# ProDocument_LTC2220_ADA_V1_2025-01-04.net
KiCad netlist of a schematic drawn in EasyEDA Pro
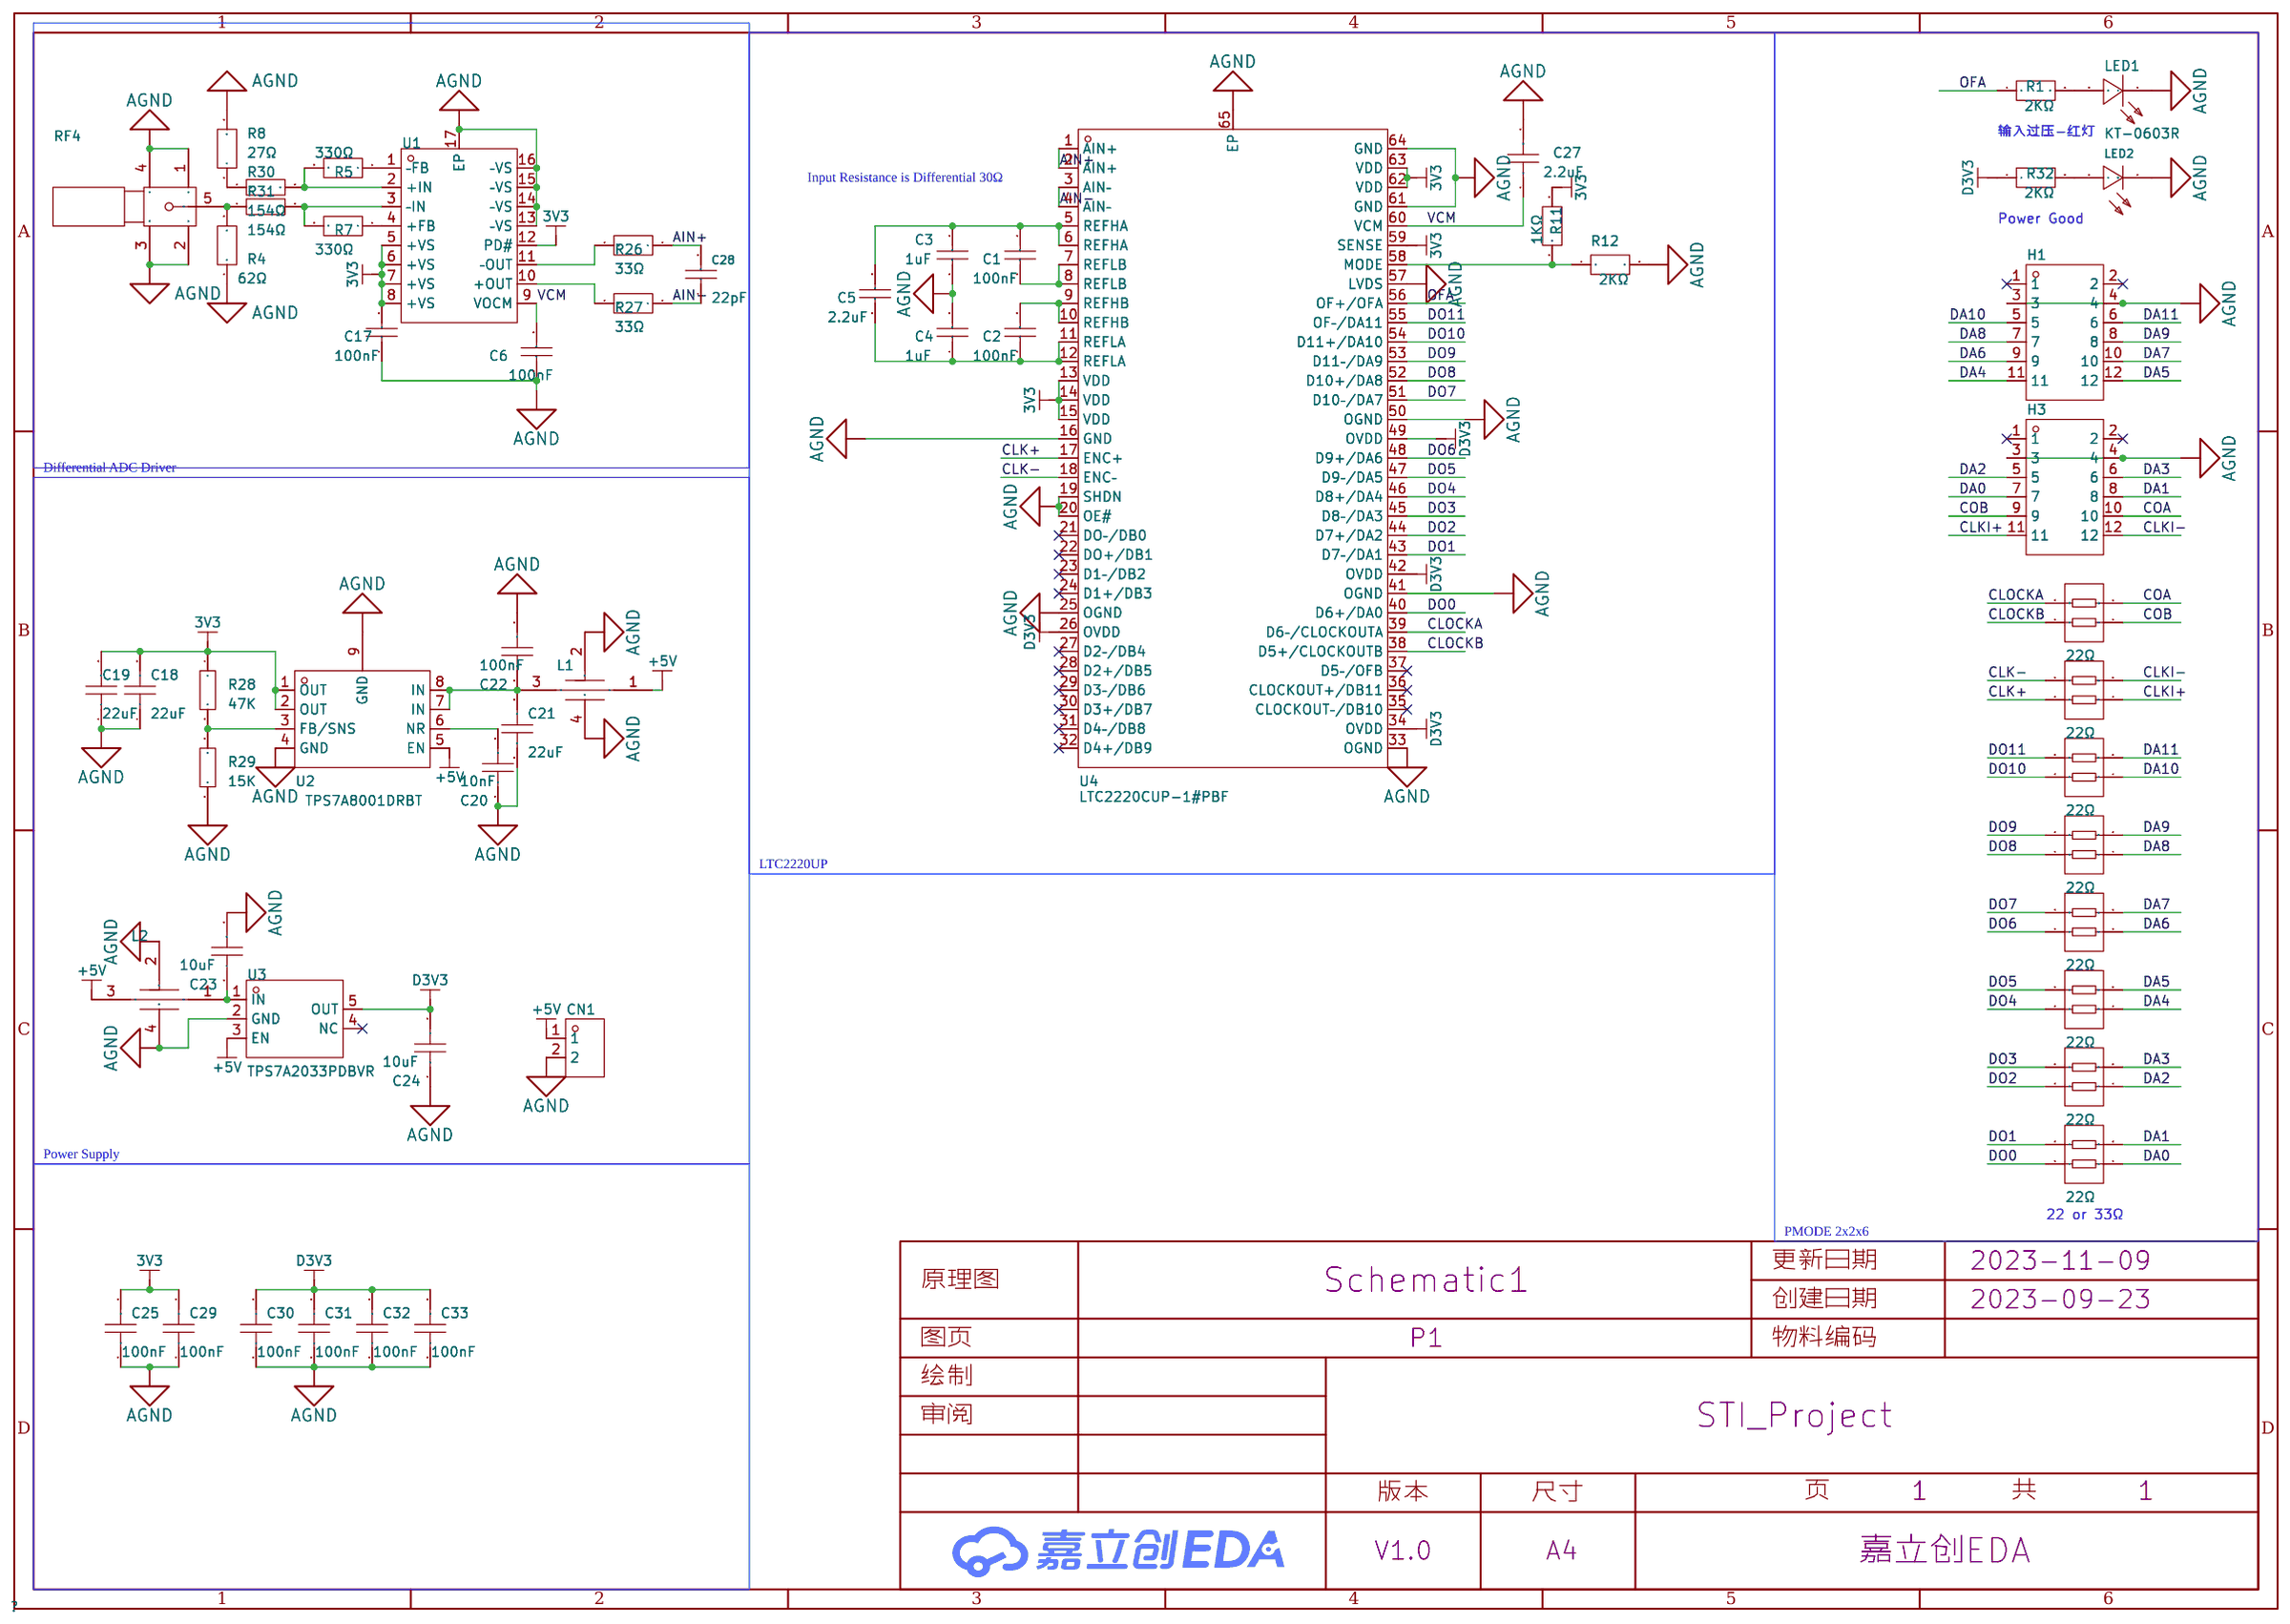
[diagram p0: schematic sheet]

(export (version "E")
  (design (tool "Eeschema 10.0.6"))
  (components
    (comp (ref "C1")
      (value "100nF")
      (footprint "easyedapro:C0402")
      (description "容值:100nF;精度:±10%;额定电压:16V;材质(温度系数):X7R;")
      (fields
        (field (name "Manufacturer Part") "GCM155R71C104KA40D")
        (field (name "Manufacturer") "muRata(村田)")
      )
      (libsource (lib "easyedapro") (part "GCM155R71C104KA40D"))
    )
    (comp (ref "C2")
      (value "100nF")
      (footprint "easyedapro:C0402")
      (description "容值:100nF;精度:±10%;额定电压:16V;材质(温度系数):X7R;")
      (fields
        (field (name "Manufacturer Part") "GCM155R71C104KA40D")
        (field (name "Manufacturer") "muRata(村田)")
      )
      (libsource (lib "easyedapro") (part "GCM155R71C104KA40D"))
    )
    (comp (ref "C3")
      (value "1uF")
      (footprint "easyedapro:C0402")
      (description "容值:100nF;精度:±10%;额定电压:16V;材质(温度系数):X7R;")
      (fields
        (field (name "Manufacturer Part") "GCM155R71C104KA40D")
        (field (name "Manufacturer") "muRata(村田)")
      )
      (libsource (lib "easyedapro") (part "GCM155R71C104KA40D"))
    )
    (comp (ref "C4")
      (value "1uF")
      (footprint "easyedapro:C0402")
      (description "容值:100nF;精度:±10%;额定电压:16V;材质(温度系数):X7R;")
      (fields
        (field (name "Manufacturer Part") "GCM155R71C104KA40D")
        (field (name "Manufacturer") "muRata(村田)")
      )
      (libsource (lib "easyedapro") (part "GCM155R71C104KA40D"))
    )
    (comp (ref "C5")
      (value "2.2uF")
      (footprint "easyedapro:C0402")
      (description "容值:100nF;精度:±10%;额定电压:16V;材质(温度系数):X7R;")
      (fields
        (field (name "Manufacturer Part") "GCM155R71C104KA40D")
        (field (name "Manufacturer") "muRata(村田)")
      )
      (libsource (lib "easyedapro") (part "GCM155R71C104KA40D"))
    )
    (comp (ref "C6")
      (value "100nF")
      (footprint "easyedapro:C0402")
      (description "容值:100nF;精度:±10%;额定电压:16V;材质(温度系数):X7R;")
      (fields
        (field (name "Manufacturer Part") "GCM155R71C104KA40D")
        (field (name "Manufacturer") "muRata(村田)")
      )
      (libsource (lib "easyedapro") (part "GCM155R71C104KA40D"))
    )
    (comp (ref "C17")
      (value "100nF")
      (footprint "easyedapro:C0402")
      (description "容值:100nF;精度:±10%;额定电压:16V;材质(温度系数):X7R;")
      (fields
        (field (name "Manufacturer Part") "GCM155R71C104KA40D")
        (field (name "Manufacturer") "muRata(村田)")
      )
      (libsource (lib "easyedapro") (part "GCM155R71C104KA40D"))
    )
    (comp (ref "C18")
      (value "22uF")
      (footprint "easyedapro:C0805")
      (description "容值:22uF;精度:±20%;额定电压:25V;材质(温度系数):X5R;")
      (fields
        (field (name "Manufacturer Part") "CL21A226MAQNNNE")
        (field (name "Manufacturer") "SAMSUNG(三星)")
      )
      (libsource (lib "easyedapro") (part "CL21A226MAQNNNE"))
    )
    (comp (ref "C19")
      (value "22uF")
      (footprint "easyedapro:C0805")
      (description "容值:22uF;精度:±20%;额定电压:25V;材质(温度系数):X5R;")
      (fields
        (field (name "Manufacturer Part") "CL21A226MAQNNNE")
        (field (name "Manufacturer") "SAMSUNG(三星)")
      )
      (libsource (lib "easyedapro") (part "CL21A226MAQNNNE"))
    )
    (comp (ref "C20")
      (value "10nF")
      (footprint "easyedapro:C0402")
      (libsource (lib "easyedapro") (part "CapAcitance"))
    )
    (comp (ref "C21")
      (value "22uF")
      (footprint "easyedapro:C0805")
      (description "容值:22uF;精度:±20%;额定电压:25V;材质(温度系数):X5R;")
      (fields
        (field (name "Manufacturer Part") "CL21A226MAQNNNE")
        (field (name "Manufacturer") "SAMSUNG(三星)")
      )
      (libsource (lib "easyedapro") (part "CL21A226MAQNNNE"))
    )
    (comp (ref "C22")
      (value "100nF")
      (footprint "easyedapro:C0402")
      (libsource (lib "easyedapro") (part "CapAcitance"))
    )
    (comp (ref "C23")
      (value "10uF")
      (footprint "easyedapro:C0402")
      (libsource (lib "easyedapro") (part "CapAcitance"))
    )
    (comp (ref "C24")
      (value "10uF")
      (footprint "easyedapro:C0402")
      (libsource (lib "easyedapro") (part "CapAcitance"))
    )
    (comp (ref "C25")
      (value "100nF")
      (footprint "easyedapro:C0402")
      (libsource (lib "easyedapro") (part "CapAcitance"))
    )
    (comp (ref "C27")
      (value "2.2uF")
      (footprint "easyedapro:C0402")
      (libsource (lib "easyedapro") (part "CapAcitance"))
    )
    (comp (ref "C28")
      (value "22pF")
      (footprint "easyedapro:C0402")
      (description "容值:22pF;精度:±5%;额定电压:50V;材质(温度系数):C0G;")
      (fields (field (name "Manufacturer Part") "0402CG220J500NT") (field (name "Manufacturer") "FH(风华)"))
      (libsource (lib "easyedapro") (part "0402CG220J500NT"))
    )
    (comp (ref "C29")
      (value "100nF")
      (footprint "easyedapro:C0402")
      (libsource (lib "easyedapro") (part "CapAcitance"))
    )
    (comp (ref "C30")
      (value "100nF")
      (footprint "easyedapro:C0402")
      (libsource (lib "easyedapro") (part "CapAcitance"))
    )
    (comp (ref "C31")
      (value "100nF")
      (footprint "easyedapro:C0402")
      (libsource (lib "easyedapro") (part "CapAcitance"))
    )
    (comp (ref "C32")
      (value "100nF")
      (footprint "easyedapro:C0402")
      (libsource (lib "easyedapro") (part "CapAcitance"))
    )
    (comp (ref "C33")
      (value "100nF")
      (footprint "easyedapro:C0402")
      (libsource (lib "easyedapro") (part "CapAcitance"))
    )
    (comp (ref "CN1")
      (value "M2510V-02P")
      (footprint "easyedapro:CONN-TH_M2510V-02P")
      (description "参考系列:-;间距:2.54mm;插针结构:1x2P;排数:1;每排PIN数:2;行距:-;公母:公型插针;安装方式:直插;额定电流:3A;工作温度范围:-25~+85;")
      (fields (field (name "Manufacturer") "XFCN(台湾兴飞)"))
      (libsource (lib "easyedapro") (part "M2510V-02P"))
    )
    (comp (ref "H1")
      (value "DZ254W-22-12-69")
      (footprint "easyedapro:HDR-TH_12P-P2.54-H-M-R2-C6-S2.54-W12.5")
      (fields (field (name "Manufacturer") "DEALON(德艺隆)"))
      (libsource (lib "easyedapro") (part "DZ254W-22-12-69"))
    )
    (comp (ref "H3")
      (value "DZ254W-22-12-69")
      (footprint "easyedapro:HDR-TH_12P-P2.54-H-M-R2-C6-S2.54-W12.5")
      (fields (field (name "Manufacturer") "DEALON(德艺隆)"))
      (libsource (lib "easyedapro") (part "DZ254W-22-12-69"))
    )
    (comp (ref "L1")
      (value "NFM21PC104R1E3D")
      (footprint "easyedapro:CAP-SMD_4P-L2.0-W1.25")
      (description "电容量:100nF;精度:±20%;直流电阻:30mΩ;")
      (fields (field (name "Manufacturer") "muRata(村田)"))
      (libsource (lib "easyedapro") (part "NFM21PC104R1E3D"))
    )
    (comp (ref "L2")
      (value "NFM21PC104R1E3D")
      (footprint "easyedapro:CAP-SMD_4P-L2.0-W1.25")
      (description "电容量:100nF;精度:±20%;直流电阻:30mΩ;")
      (fields (field (name "Manufacturer") "muRata(村田)"))
      (libsource (lib "easyedapro") (part "NFM21PC104R1E3D"))
    )
    (comp (ref "LED1")
      (value "KT-0603R")
      (footprint "easyedapro:LED0603-RD")
      (description "发光颜色:红灯;二极管配置:-;透镜颜色:-;主波长:-;色温:-;功率:-;发光角度:-;安装方式:-;工作温度:-40°C~+85°C;")
      (fields (field (name "Manufacturer") "KENTO"))
      (libsource (lib "easyedapro") (part "KT-0603R"))
    )
    (comp (ref "LED2")
      (value "19-217/GHC-YR1S2/3T")
      (footprint "easyedapro:LED0603-RD")
      (description "发光颜色:翠绿;二极管配置:-;主波长:520nm~535nm;色温:-;功率:110mW;安装方式:-;")
      (fields (field (name "Manufacturer") "EVERLIGHT(亿光)"))
      (libsource (lib "easyedapro") (part "19-217/GHC-YR1S2/3T"))
    )
    (comp (ref "R1")
      (value "2KΩ")
      (footprint "easyedapro:R0402")
      (description "阻值:1kΩ;精度:±0.1%;温度系数:±25ppm/;")
      (fields (field (name "Manufacturer Part") "ARG02BTC1001") (field (name "Manufacturer") "Viking(光颉)"))
      (libsource (lib "easyedapro") (part "ARG02BTC1001"))
    )
    (comp (ref "R4")
      (value "62Ω")
      (footprint "easyedapro:R0402")
      (description "阻值:1kΩ;精度:±0.1%;温度系数:±25ppm/;")
      (fields (field (name "Manufacturer Part") "ARG02BTC1001") (field (name "Manufacturer") "Viking(光颉)"))
      (libsource (lib "easyedapro") (part "ARG02BTC1001"))
    )
    (comp (ref "R5")
      (value "330Ω")
      (footprint "easyedapro:R0402")
      (description "阻值:1kΩ;精度:±0.1%;温度系数:±25ppm/;")
      (fields (field (name "Manufacturer Part") "ARG02BTC1001") (field (name "Manufacturer") "Viking(光颉)"))
      (libsource (lib "easyedapro") (part "ARG02BTC1001"))
    )
    (comp (ref "R7")
      (value "330Ω")
      (footprint "easyedapro:R0402")
      (description "阻值:1kΩ;精度:±0.1%;温度系数:±25ppm/;")
      (fields (field (name "Manufacturer Part") "ARG02BTC1001") (field (name "Manufacturer") "Viking(光颉)"))
      (libsource (lib "easyedapro") (part "ARG02BTC1001"))
    )
    (comp (ref "R8")
      (value "27Ω")
      (footprint "easyedapro:R0402")
      (description "阻值:1kΩ;精度:±0.1%;温度系数:±25ppm/;")
      (fields (field (name "Manufacturer Part") "ARG02BTC1001") (field (name "Manufacturer") "Viking(光颉)"))
      (libsource (lib "easyedapro") (part "ARG02BTC1001"))
    )
    (comp (ref "R11")
      (value "1KΩ")
      (footprint "easyedapro:R0402")
      (description "阻值:1kΩ;精度:±0.1%;温度系数:±25ppm/;")
      (fields (field (name "Manufacturer Part") "ARG02BTC1001") (field (name "Manufacturer") "Viking(光颉)"))
      (libsource (lib "easyedapro") (part "ARG02BTC1001"))
    )
    (comp (ref "R12")
      (value "2KΩ")
      (footprint "easyedapro:R0402")
      (description "阻值:1kΩ;精度:±0.1%;温度系数:±25ppm/;")
      (fields (field (name "Manufacturer Part") "ARG02BTC1001") (field (name "Manufacturer") "Viking(光颉)"))
      (libsource (lib "easyedapro") (part "ARG02BTC1001"))
    )
    (comp (ref "R26")
      (value "33Ω")
      (footprint "easyedapro:R0402")
      (description "阻值:1kΩ;精度:±0.1%;温度系数:±25ppm/;")
      (fields (field (name "Manufacturer Part") "ARG02BTC1001") (field (name "Manufacturer") "Viking(光颉)"))
      (libsource (lib "easyedapro") (part "ARG02BTC1001"))
    )
    (comp (ref "R27")
      (value "33Ω")
      (footprint "easyedapro:R0402")
      (description "阻值:1kΩ;精度:±0.1%;温度系数:±25ppm/;")
      (fields (field (name "Manufacturer Part") "ARG02BTC1001") (field (name "Manufacturer") "Viking(光颉)"))
      (libsource (lib "easyedapro") (part "ARG02BTC1001"))
    )
    (comp (ref "R28") (value "47K") (footprint "easyedapro:R0402") (libsource (lib "easyedapro") (part "电阻")))
    (comp (ref "R29") (value "15K") (footprint "easyedapro:R0402") (libsource (lib "easyedapro") (part "电阻")))
    (comp (ref "R30")
      (value "154Ω")
      (footprint "easyedapro:R0402")
      (description "电阻类型:厚膜电阻;阻值:154Ω;精度:±1%;功率:62.5mW;")
      (fields (field (name "Manufacturer Part") "AC0402FR-07154RL") (field (name "Manufacturer") "YAGEO(国巨)"))
      (libsource (lib "easyedapro") (part "AC0402FR-07154RL"))
    )
    (comp (ref "R31")
      (value "154Ω")
      (footprint "easyedapro:R0402")
      (description "电阻类型:厚膜电阻;阻值:154Ω;精度:±1%;功率:62.5mW;")
      (fields (field (name "Manufacturer Part") "AC0402FR-07154RL") (field (name "Manufacturer") "YAGEO(国巨)"))
      (libsource (lib "easyedapro") (part "AC0402FR-07154RL"))
    )
    (comp (ref "R32")
      (value "2KΩ")
      (footprint "easyedapro:R0402")
      (description "阻值:1kΩ;精度:±0.1%;温度系数:±25ppm/;")
      (fields (field (name "Manufacturer Part") "ARG02BTC1001") (field (name "Manufacturer") "Viking(光颉)"))
      (libsource (lib "easyedapro") (part "ARG02BTC1001"))
    )
    (comp (ref "RF4")
      (value "KH-SMA-KE5.4")
      (footprint "easyedapro:SMA-TH_KH-SMA-KE-Z")
      (description "SMA板端 SMA板端 镀金半牙正脚直插SMA母针板端L=16.8MM 牙长5.4MM")
      (fields (field (name "Manufacturer") "kinghelm(金航标)"))
      (libsource (lib "easyedapro") (part "KH-SMA-KE5.4"))
    )
    (comp (ref "RN1")
      (value "22Ω")
      (footprint "easyedapro:RES-ARRAY-SMD_0402-4P-L1.0-W1.0-BL")
      (description "阻值:22Ω;精度:±1%;单个元件功率:62.5mW;电阻器数:2;")
      (fields
        (field (name "Manufacturer Part") "2D02WGF220JTCE")
        (field (name "Manufacturer") "UNI-ROYAL(厚声)")
      )
      (libsource (lib "easyedapro") (part "2D02WGF220JTCE"))
    )
    (comp (ref "RN2")
      (value "22Ω")
      (footprint "easyedapro:RES-ARRAY-SMD_0402-4P-L1.0-W1.0-BL")
      (description "阻值:22Ω;精度:±1%;单个元件功率:62.5mW;电阻器数:2;")
      (fields
        (field (name "Manufacturer Part") "2D02WGF220JTCE")
        (field (name "Manufacturer") "UNI-ROYAL(厚声)")
      )
      (libsource (lib "easyedapro") (part "2D02WGF220JTCE"))
    )
    (comp (ref "RN3")
      (value "22Ω")
      (footprint "easyedapro:RES-ARRAY-SMD_0402-4P-L1.0-W1.0-BL")
      (description "阻值:22Ω;精度:±1%;单个元件功率:62.5mW;电阻器数:2;")
      (fields
        (field (name "Manufacturer Part") "2D02WGF220JTCE")
        (field (name "Manufacturer") "UNI-ROYAL(厚声)")
      )
      (libsource (lib "easyedapro") (part "2D02WGF220JTCE"))
    )
    (comp (ref "RN4")
      (value "22Ω")
      (footprint "easyedapro:RES-ARRAY-SMD_0402-4P-L1.0-W1.0-BL")
      (description "阻值:22Ω;精度:±1%;单个元件功率:62.5mW;电阻器数:2;")
      (fields
        (field (name "Manufacturer Part") "2D02WGF220JTCE")
        (field (name "Manufacturer") "UNI-ROYAL(厚声)")
      )
      (libsource (lib "easyedapro") (part "2D02WGF220JTCE"))
    )
    (comp (ref "RN5")
      (value "22Ω")
      (footprint "easyedapro:RES-ARRAY-SMD_0402-4P-L1.0-W1.0-BL")
      (description "阻值:22Ω;精度:±1%;单个元件功率:62.5mW;电阻器数:2;")
      (fields
        (field (name "Manufacturer Part") "2D02WGF220JTCE")
        (field (name "Manufacturer") "UNI-ROYAL(厚声)")
      )
      (libsource (lib "easyedapro") (part "2D02WGF220JTCE"))
    )
    (comp (ref "RN6")
      (value "22Ω")
      (footprint "easyedapro:RES-ARRAY-SMD_0402-4P-L1.0-W1.0-BL")
      (description "阻值:22Ω;精度:±1%;单个元件功率:62.5mW;电阻器数:2;")
      (fields
        (field (name "Manufacturer Part") "2D02WGF220JTCE")
        (field (name "Manufacturer") "UNI-ROYAL(厚声)")
      )
      (libsource (lib "easyedapro") (part "2D02WGF220JTCE"))
    )
    (comp (ref "RN7")
      (value "22Ω")
      (footprint "easyedapro:RES-ARRAY-SMD_0402-4P-L1.0-W1.0-BL")
      (description "阻值:22Ω;精度:±1%;单个元件功率:62.5mW;电阻器数:2;")
      (fields
        (field (name "Manufacturer Part") "2D02WGF220JTCE")
        (field (name "Manufacturer") "UNI-ROYAL(厚声)")
      )
      (libsource (lib "easyedapro") (part "2D02WGF220JTCE"))
    )
    (comp (ref "RN8")
      (value "22Ω")
      (footprint "easyedapro:RES-ARRAY-SMD_0402-4P-L1.0-W1.0-BL")
      (description "阻值:22Ω;精度:±1%;单个元件功率:62.5mW;电阻器数:2;")
      (fields
        (field (name "Manufacturer Part") "2D02WGF220JTCE")
        (field (name "Manufacturer") "UNI-ROYAL(厚声)")
      )
      (libsource (lib "easyedapro") (part "2D02WGF220JTCE"))
    )
    (comp (ref "U1")
      (value "ADA4937-1YCPZ-RL")
      (footprint "easyedapro:LFCSP-16_L3.0-W3.0-P0.50-BL-EP1.3")
      (description "ADC-驱动器-IC-数据采集-16-LFCSP-VQ（3x3）")
      (fields (field (name "Manufacturer") "ADI(亚德诺)/LINEAR"))
      (libsource (lib "easyedapro") (part "ADA4937-1YCPZ-RL"))
    )
    (comp (ref "U2")
      (value "TPS7A8001DRBT")
      (footprint "easyedapro:SON-8_L3.0-W3.0-P0.65-BL-EP")
      (description "输出类型:可调;输出极性:正;输出通道数:1;最大输入电压:6.5V;输出电压:0.8V~6V;压差:500mV@(1A);输出电流:1A;电源纹波抑制比(PSRR):63dB;")
      (fields (field (name "Manufacturer") "TI(德州仪器)"))
      (libsource (lib "easyedapro") (part "TPS7A8001DRBT"))
    )
    (comp (ref "U3")
      (value "TPS7A2033PDBVR")
      (footprint "easyedapro:SOT-23-5_L2.9-W1.6-P0.95-LS2.8-BR")
      (fields (field (name "Manufacturer") "TI(德州仪器)"))
      (libsource (lib "easyedapro") (part "TPS7A2033PDBVR"))
    )
    (comp (ref "U4")
      (value "LTC2220CUP-1#PBF")
      (footprint "easyedapro:QFN-64_L9.0-W9.0-P0.50-BL-EP7.2")
      (description "A/D 位数:-;采样率（sps）:-;输入数:-;输入类型:-;")
      (fields (field (name "Manufacturer") "ADI(亚德诺)/LINEAR"))
      (libsource (lib "easyedapro") (part "LTC2220CUP-1#PBF"))
    )
  )
  (nets
    (net (code "1") (name "+5V") (class "Default")
      (node (ref "CN1") (pin "1") (pinfunction "1_1") (pintype "input"))
      (node (ref "L1") (pin "1") (pinfunction "IN_1") (pintype "input"))
      (node (ref "L2") (pin "3") (pinfunction "OUT_3") (pintype "input"))
      (node (ref "U2") (pin "5") (pinfunction "EN_5") (pintype "input"))
      (node (ref "U3") (pin "3") (pinfunction "EN_3") (pintype "input"))
    )
    (net (code "2") (name "/AIN+") (class "Default")
      (node (ref "C28") (pin "2") (pinfunction "2_2") (pintype "input"))
      (node (ref "R26") (pin "1") (pinfunction "1_1") (pintype "input"))
      (node (ref "U4") (pin "1") (pinfunction "AIN+_1") (pintype "input"))
      (node (ref "U4") (pin "2") (pinfunction "AIN+_2") (pintype "input"))
    )
    (net (code "3") (name "/AIN-") (class "Default")
      (node (ref "C28") (pin "1") (pinfunction "1_1") (pintype "input"))
      (node (ref "R27") (pin "1") (pinfunction "1_1") (pintype "input"))
      (node (ref "U4") (pin "3") (pinfunction "AIN–_3") (pintype "input"))
      (node (ref "U4") (pin "4") (pinfunction "AIN–_4") (pintype "input"))
    )
    (net (code "4") (name "/CLK+") (class "Default")
      (node (ref "RN2") (pin "1") (pinfunction "1_1") (pintype "input"))
      (node (ref "U4") (pin "17") (pinfunction "ENC+_17") (pintype "input"))
    )
    (net (code "5") (name "/CLK-") (class "Default")
      (node (ref "RN2") (pin "2") (pinfunction "2_2") (pintype "input"))
      (node (ref "U4") (pin "18") (pinfunction "ENC–_18") (pintype "input"))
    )
    (net (code "6") (name "/CLKI+") (class "Default")
      (node (ref "H3") (pin "11") (pinfunction "11_11") (pintype "input"))
      (node (ref "RN2") (pin "4") (pinfunction "4_4") (pintype "input"))
    )
    (net (code "7") (name "/CLKI-") (class "Default")
      (node (ref "H3") (pin "12") (pinfunction "12_12") (pintype "input"))
      (node (ref "RN2") (pin "3") (pinfunction "3_3") (pintype "input"))
    )
    (net (code "8") (name "/CLOCKA") (class "Default")
      (node (ref "RN8") (pin "2") (pinfunction "2_2") (pintype "input"))
      (node (ref "U4") (pin "39") (pinfunction "D6–/CLOCKOUTA_39") (pintype "input"))
    )
    (net (code "9") (name "/CLOCKB") (class "Default")
      (node (ref "RN8") (pin "1") (pinfunction "1_1") (pintype "input"))
      (node (ref "U4") (pin "38") (pinfunction "D5+/CLOCKOUTB_38") (pintype "input"))
    )
    (net (code "10") (name "/COA") (class "Default")
      (node (ref "H3") (pin "10") (pinfunction "10_10") (pintype "input"))
      (node (ref "RN8") (pin "3") (pinfunction "3_3") (pintype "input"))
    )
    (net (code "11") (name "/COB") (class "Default")
      (node (ref "H3") (pin "9") (pinfunction "9_9") (pintype "input"))
      (node (ref "RN8") (pin "4") (pinfunction "4_4") (pintype "input"))
    )
    (net (code "12") (name "/DA0") (class "Default")
      (node (ref "H3") (pin "7") (pinfunction "7_7") (pintype "input"))
      (node (ref "RN7") (pin "4") (pinfunction "4_4") (pintype "input"))
    )
    (net (code "13") (name "/DA1") (class "Default")
      (node (ref "H3") (pin "8") (pinfunction "8_8") (pintype "input"))
      (node (ref "RN7") (pin "3") (pinfunction "3_3") (pintype "input"))
    )
    (net (code "14") (name "/DA2") (class "Default")
      (node (ref "H3") (pin "5") (pinfunction "5_5") (pintype "input"))
      (node (ref "RN6") (pin "4") (pinfunction "4_4") (pintype "input"))
    )
    (net (code "15") (name "/DA3") (class "Default")
      (node (ref "H3") (pin "6") (pinfunction "6_6") (pintype "input"))
      (node (ref "RN6") (pin "3") (pinfunction "3_3") (pintype "input"))
    )
    (net (code "16") (name "/DA4") (class "Default")
      (node (ref "H1") (pin "11") (pinfunction "11_11") (pintype "input"))
      (node (ref "RN5") (pin "4") (pinfunction "4_4") (pintype "input"))
    )
    (net (code "17") (name "/DA5") (class "Default")
      (node (ref "H1") (pin "12") (pinfunction "12_12") (pintype "input"))
      (node (ref "RN5") (pin "3") (pinfunction "3_3") (pintype "input"))
    )
    (net (code "18") (name "/DA6") (class "Default")
      (node (ref "H1") (pin "9") (pinfunction "9_9") (pintype "input"))
      (node (ref "RN4") (pin "4") (pinfunction "4_4") (pintype "input"))
    )
    (net (code "19") (name "/DA7") (class "Default")
      (node (ref "H1") (pin "10") (pinfunction "10_10") (pintype "input"))
      (node (ref "RN4") (pin "3") (pinfunction "3_3") (pintype "input"))
    )
    (net (code "20") (name "/DA8") (class "Default")
      (node (ref "H1") (pin "7") (pinfunction "7_7") (pintype "input"))
      (node (ref "RN3") (pin "4") (pinfunction "4_4") (pintype "input"))
    )
    (net (code "21") (name "/DA9") (class "Default")
      (node (ref "H1") (pin "8") (pinfunction "8_8") (pintype "input"))
      (node (ref "RN3") (pin "3") (pinfunction "3_3") (pintype "input"))
    )
    (net (code "22") (name "/DA10") (class "Default")
      (node (ref "H1") (pin "5") (pinfunction "5_5") (pintype "input"))
      (node (ref "RN1") (pin "4") (pinfunction "4_4") (pintype "input"))
    )
    (net (code "23") (name "/DA11") (class "Default")
      (node (ref "H1") (pin "6") (pinfunction "6_6") (pintype "input"))
      (node (ref "RN1") (pin "3") (pinfunction "3_3") (pintype "input"))
    )
    (net (code "24") (name "/DO0") (class "Default")
      (node (ref "RN7") (pin "1") (pinfunction "1_1") (pintype "input"))
      (node (ref "U4") (pin "40") (pinfunction "D6+/DA0_40") (pintype "input"))
    )
    (net (code "25") (name "/DO1") (class "Default")
      (node (ref "RN7") (pin "2") (pinfunction "2_2") (pintype "input"))
      (node (ref "U4") (pin "43") (pinfunction "D7–/DA1_43") (pintype "input"))
    )
    (net (code "26") (name "/DO2") (class "Default")
      (node (ref "RN6") (pin "1") (pinfunction "1_1") (pintype "input"))
      (node (ref "U4") (pin "44") (pinfunction "D7+/DA2_44") (pintype "input"))
    )
    (net (code "27") (name "/DO3") (class "Default")
      (node (ref "RN6") (pin "2") (pinfunction "2_2") (pintype "input"))
      (node (ref "U4") (pin "45") (pinfunction "D8–/DA3_45") (pintype "input"))
    )
    (net (code "28") (name "/DO4") (class "Default")
      (node (ref "RN5") (pin "1") (pinfunction "1_1") (pintype "input"))
      (node (ref "U4") (pin "46") (pinfunction "D8+/DA4_46") (pintype "input"))
    )
    (net (code "29") (name "/DO5") (class "Default")
      (node (ref "RN5") (pin "2") (pinfunction "2_2") (pintype "input"))
      (node (ref "U4") (pin "47") (pinfunction "D9–/DA5_47") (pintype "input"))
    )
    (net (code "30") (name "/DO6") (class "Default")
      (node (ref "RN4") (pin "1") (pinfunction "1_1") (pintype "input"))
      (node (ref "U4") (pin "48") (pinfunction "D9+/DA6_48") (pintype "input"))
    )
    (net (code "31") (name "/DO7") (class "Default")
      (node (ref "RN4") (pin "2") (pinfunction "2_2") (pintype "input"))
      (node (ref "U4") (pin "51") (pinfunction "D10–/DA7_51") (pintype "input"))
    )
    (net (code "32") (name "/DO8") (class "Default")
      (node (ref "RN3") (pin "1") (pinfunction "1_1") (pintype "input"))
      (node (ref "U4") (pin "52") (pinfunction "D10+/DA8_52") (pintype "input"))
    )
    (net (code "33") (name "/DO9") (class "Default")
      (node (ref "RN3") (pin "2") (pinfunction "2_2") (pintype "input"))
      (node (ref "U4") (pin "53") (pinfunction "D11–/DA9_53") (pintype "input"))
    )
    (net (code "34") (name "/DO10") (class "Default")
      (node (ref "RN1") (pin "1") (pinfunction "1_1") (pintype "input"))
      (node (ref "U4") (pin "54") (pinfunction "D11+/DA10_54") (pintype "input"))
    )
    (net (code "35") (name "/DO11") (class "Default")
      (node (ref "RN1") (pin "2") (pinfunction "2_2") (pintype "input"))
      (node (ref "U4") (pin "55") (pinfunction "OF–/DA11_55") (pintype "input"))
    )
    (net (code "36") (name "/OFA") (class "Default")
      (node (ref "R1") (pin "1") (pinfunction "1_1") (pintype "input"))
      (node (ref "U4") (pin "56") (pinfunction "OF+/OFA_56") (pintype "input"))
    )
    (net (code "37") (name "/VCM") (class "Default")
      (node (ref "C27") (pin "1") (pinfunction "1_1") (pintype "input"))
      (node (ref "C6") (pin "2") (pinfunction "2_2") (pintype "input"))
      (node (ref "U1") (pin "9") (pinfunction "VOCM_9") (pintype "input"))
      (node (ref "U4") (pin "60") (pinfunction "VCM_60") (pintype "input"))
    )
    (net (code "38") (name "3V3") (class "Default")
      (node (ref "C17") (pin "2") (pinfunction "2_2") (pintype "input"))
      (node (ref "C18") (pin "2") (pinfunction "2_2") (pintype "input"))
      (node (ref "C19") (pin "2") (pinfunction "2_2") (pintype "input"))
      (node (ref "C25") (pin "2") (pinfunction "2_2") (pintype "input"))
      (node (ref "C29") (pin "2") (pinfunction "2_2") (pintype "input"))
      (node (ref "R11") (pin "1") (pinfunction "1_1") (pintype "input"))
      (node (ref "R28") (pin "1") (pinfunction "1_1") (pintype "input"))
      (node (ref "U1") (pin "12") (pinfunction "PD#_12") (pintype "input"))
      (node (ref "U1") (pin "5") (pinfunction "+VS_5") (pintype "input"))
      (node (ref "U1") (pin "6") (pinfunction "+VS_6") (pintype "input"))
      (node (ref "U1") (pin "7") (pinfunction "+VS_7") (pintype "input"))
      (node (ref "U1") (pin "8") (pinfunction "+VS_8") (pintype "input"))
      (node (ref "U2") (pin "1") (pinfunction "OUT_1") (pintype "input"))
      (node (ref "U2") (pin "2") (pinfunction "OUT_2") (pintype "input"))
      (node (ref "U4") (pin "13") (pinfunction "VDD_13") (pintype "input"))
      (node (ref "U4") (pin "14") (pinfunction "VDD_14") (pintype "input"))
      (node (ref "U4") (pin "15") (pinfunction "VDD_15") (pintype "input"))
      (node (ref "U4") (pin "59") (pinfunction "SENSE_59") (pintype "input"))
      (node (ref "U4") (pin "62") (pinfunction "VDD_62") (pintype "input"))
      (node (ref "U4") (pin "63") (pinfunction "VDD_63") (pintype "input"))
    )
    (net (code "39") (name "AGND") (class "Default")
      (node (ref "C17") (pin "1") (pinfunction "1_1") (pintype "input"))
      (node (ref "C18") (pin "1") (pinfunction "1_1") (pintype "input"))
      (node (ref "C19") (pin "1") (pinfunction "1_1") (pintype "input"))
      (node (ref "C20") (pin "1") (pinfunction "1_1") (pintype "input"))
      (node (ref "C21") (pin "1") (pinfunction "1_1") (pintype "input"))
      (node (ref "C22") (pin "2") (pinfunction "2_2") (pintype "input"))
      (node (ref "C23") (pin "2") (pinfunction "2_2") (pintype "input"))
      (node (ref "C24") (pin "1") (pinfunction "1_1") (pintype "input"))
      (node (ref "C25") (pin "1") (pinfunction "1_1") (pintype "input"))
      (node (ref "C27") (pin "2") (pinfunction "2_2") (pintype "input"))
      (node (ref "C29") (pin "1") (pinfunction "1_1") (pintype "input"))
      (node (ref "C3") (pin "1") (pinfunction "1_1") (pintype "input"))
      (node (ref "C30") (pin "1") (pinfunction "1_1") (pintype "input"))
      (node (ref "C31") (pin "1") (pinfunction "1_1") (pintype "input"))
      (node (ref "C32") (pin "1") (pinfunction "1_1") (pintype "input"))
      (node (ref "C33") (pin "1") (pinfunction "1_1") (pintype "input"))
      (node (ref "C4") (pin "2") (pinfunction "2_2") (pintype "input"))
      (node (ref "C6") (pin "1") (pinfunction "1_1") (pintype "input"))
      (node (ref "CN1") (pin "2") (pinfunction "2_2") (pintype "input"))
      (node (ref "H1") (pin "3") (pinfunction "3_3") (pintype "input"))
      (node (ref "H1") (pin "4") (pinfunction "4_4") (pintype "input"))
      (node (ref "H3") (pin "3") (pinfunction "3_3") (pintype "input"))
      (node (ref "H3") (pin "4") (pinfunction "4_4") (pintype "input"))
      (node (ref "L1") (pin "2") (pinfunction "GND_2") (pintype "input"))
      (node (ref "L1") (pin "4") (pinfunction "GND_4") (pintype "input"))
      (node (ref "L2") (pin "2") (pinfunction "GND_2") (pintype "input"))
      (node (ref "L2") (pin "4") (pinfunction "GND_4") (pintype "input"))
      (node (ref "LED1") (pin "1") (pinfunction "K_1") (pintype "input"))
      (node (ref "LED2") (pin "1") (pinfunction "C_1") (pintype "input"))
      (node (ref "R12") (pin "2") (pinfunction "2_2") (pintype "input"))
      (node (ref "R29") (pin "2") (pinfunction "2_2") (pintype "input"))
      (node (ref "R4") (pin "1") (pinfunction "1_1") (pintype "input"))
      (node (ref "R8") (pin "2") (pinfunction "2_2") (pintype "input"))
      (node (ref "RF4") (pin "1") (pinfunction "1_1") (pintype "input"))
      (node (ref "RF4") (pin "2") (pinfunction "2_2") (pintype "input"))
      (node (ref "RF4") (pin "3") (pinfunction "3_3") (pintype "input"))
      (node (ref "RF4") (pin "4") (pinfunction "4_4") (pintype "input"))
      (node (ref "U1") (pin "13") (pinfunction "–VS_13") (pintype "input"))
      (node (ref "U1") (pin "14") (pinfunction "–VS_14") (pintype "input"))
      (node (ref "U1") (pin "15") (pinfunction "–VS_15") (pintype "input"))
      (node (ref "U1") (pin "16") (pinfunction "–VS_16") (pintype "input"))
      (node (ref "U1") (pin "17") (pinfunction "EP_17") (pintype "input"))
      (node (ref "U2") (pin "4") (pinfunction "GND_4") (pintype "input"))
      (node (ref "U2") (pin "9") (pinfunction "GND_9") (pintype "input"))
      (node (ref "U3") (pin "2") (pinfunction "GND_2") (pintype "input"))
      (node (ref "U4") (pin "16") (pinfunction "GND_16") (pintype "input"))
      (node (ref "U4") (pin "19") (pinfunction "SHDN_19") (pintype "input"))
      (node (ref "U4") (pin "20") (pinfunction "OE#_20") (pintype "input"))
      (node (ref "U4") (pin "25") (pinfunction "OGND_25") (pintype "input"))
      (node (ref "U4") (pin "33") (pinfunction "OGND_33") (pintype "input"))
      (node (ref "U4") (pin "41") (pinfunction "OGND_41") (pintype "input"))
      (node (ref "U4") (pin "50") (pinfunction "OGND_50") (pintype "input"))
      (node (ref "U4") (pin "57") (pinfunction "LVDS_57") (pintype "input"))
      (node (ref "U4") (pin "61") (pinfunction "GND_61") (pintype "input"))
      (node (ref "U4") (pin "64") (pinfunction "GND_64") (pintype "input"))
      (node (ref "U4") (pin "65") (pinfunction "EP_65") (pintype "input"))
    )
    (net (code "40") (name "D3V3") (class "Default")
      (node (ref "C24") (pin "2") (pinfunction "2_2") (pintype "input"))
      (node (ref "C30") (pin "2") (pinfunction "2_2") (pintype "input"))
      (node (ref "C31") (pin "2") (pinfunction "2_2") (pintype "input"))
      (node (ref "C32") (pin "2") (pinfunction "2_2") (pintype "input"))
      (node (ref "C33") (pin "2") (pinfunction "2_2") (pintype "input"))
      (node (ref "R32") (pin "1") (pinfunction "1_1") (pintype "input"))
      (node (ref "U3") (pin "5") (pinfunction "OUT_5") (pintype "input"))
      (node (ref "U4") (pin "26") (pinfunction "OVDD_26") (pintype "input"))
      (node (ref "U4") (pin "34") (pinfunction "OVDD_34") (pintype "input"))
      (node (ref "U4") (pin "42") (pinfunction "OVDD_42") (pintype "input"))
      (node (ref "U4") (pin "49") (pinfunction "OVDD_49") (pintype "input"))
    )
    (net (code "41") (name "Net-(C1-Pad1)") (class "Default")
      (node (ref "C1") (pin "1") (pinfunction "1_1") (pintype "input"))
      (node (ref "U4") (pin "7") (pinfunction "REFLB_7") (pintype "input"))
      (node (ref "U4") (pin "8") (pinfunction "REFLB_8") (pintype "input"))
    )
    (net (code "42") (name "Net-(C1-Pad2)") (class "Default")
      (node (ref "C1") (pin "2") (pinfunction "2_2") (pintype "input"))
      (node (ref "C3") (pin "2") (pinfunction "2_2") (pintype "input"))
      (node (ref "C5") (pin "2") (pinfunction "2_2") (pintype "input"))
      (node (ref "U4") (pin "5") (pinfunction "REFHA_5") (pintype "input"))
      (node (ref "U4") (pin "6") (pinfunction "REFHA_6") (pintype "input"))
    )
    (net (code "43") (name "Net-(C2-Pad1)") (class "Default")
      (node (ref "C2") (pin "1") (pinfunction "1_1") (pintype "input"))
      (node (ref "C4") (pin "1") (pinfunction "1_1") (pintype "input"))
      (node (ref "C5") (pin "1") (pinfunction "1_1") (pintype "input"))
      (node (ref "U4") (pin "11") (pinfunction "REFLA_11") (pintype "input"))
      (node (ref "U4") (pin "12") (pinfunction "REFLA_12") (pintype "input"))
    )
    (net (code "44") (name "Net-(C2-Pad2)") (class "Default")
      (node (ref "C2") (pin "2") (pinfunction "2_2") (pintype "input"))
      (node (ref "U4") (pin "10") (pinfunction "REFHB_10") (pintype "input"))
      (node (ref "U4") (pin "9") (pinfunction "REFHB_9") (pintype "input"))
    )
    (net (code "45") (name "Net-(L1-OUT)") (class "Default")
      (node (ref "C21") (pin "2") (pinfunction "2_2") (pintype "input"))
      (node (ref "C22") (pin "1") (pinfunction "1_1") (pintype "input"))
      (node (ref "L1") (pin "3") (pinfunction "OUT_3") (pintype "input"))
      (node (ref "U2") (pin "7") (pinfunction "IN_7") (pintype "input"))
      (node (ref "U2") (pin "8") (pinfunction "IN_8") (pintype "input"))
    )
    (net (code "46") (name "Net-(L2-IN)") (class "Default")
      (node (ref "C23") (pin "1") (pinfunction "1_1") (pintype "input"))
      (node (ref "L2") (pin "1") (pinfunction "IN_1") (pintype "input"))
      (node (ref "U3") (pin "1") (pinfunction "IN_1") (pintype "input"))
    )
    (net (code "47") (name "Net-(LED1-A)") (class "Default")
      (node (ref "LED1") (pin "2") (pinfunction "A_2") (pintype "input"))
      (node (ref "R1") (pin "2") (pinfunction "2_2") (pintype "input"))
    )
    (net (code "48") (name "Net-(LED2-A)") (class "Default")
      (node (ref "LED2") (pin "2") (pinfunction "A_2") (pintype "input"))
      (node (ref "R32") (pin "2") (pinfunction "2_2") (pintype "input"))
    )
    (net (code "49") (name "Net-(R30-Pad1)") (class "Default")
      (node (ref "R30") (pin "1") (pinfunction "1_1") (pintype "input"))
      (node (ref "R8") (pin "1") (pinfunction "1_1") (pintype "input"))
    )
    (net (code "50") (name "Net-(R31-Pad1)") (class "Default")
      (node (ref "R31") (pin "1") (pinfunction "1_1") (pintype "input"))
      (node (ref "R4") (pin "2") (pinfunction "2_2") (pintype "input"))
      (node (ref "RF4") (pin "5") (pinfunction "5_5") (pintype "input"))
    )
    (net (code "51") (name "Net-(U1-+FB)") (class "Default")
      (node (ref "R7") (pin "1") (pinfunction "1_1") (pintype "input"))
      (node (ref "U1") (pin "4") (pinfunction "+FB_4") (pintype "input"))
    )
    (net (code "52") (name "Net-(U1-+IN)") (class "Default")
      (node (ref "R30") (pin "2") (pinfunction "2_2") (pintype "input"))
      (node (ref "R5") (pin "2") (pinfunction "2_2") (pintype "input"))
      (node (ref "U1") (pin "2") (pinfunction "+IN_2") (pintype "input"))
    )
    (net (code "53") (name "Net-(U1-+OUT)") (class "Default")
      (node (ref "R27") (pin "2") (pinfunction "2_2") (pintype "input"))
      (node (ref "U1") (pin "10") (pinfunction "+OUT_10") (pintype "input"))
    )
    (net (code "54") (name "Net-(U1-–FB)") (class "Default")
      (node (ref "R5") (pin "1") (pinfunction "1_1") (pintype "input"))
      (node (ref "U1") (pin "1") (pinfunction "–FB_1") (pintype "input"))
    )
    (net (code "55") (name "Net-(U1-–IN)") (class "Default")
      (node (ref "R31") (pin "2") (pinfunction "2_2") (pintype "input"))
      (node (ref "R7") (pin "2") (pinfunction "2_2") (pintype "input"))
      (node (ref "U1") (pin "3") (pinfunction "–IN_3") (pintype "input"))
    )
    (net (code "56") (name "Net-(U1-–OUT)") (class "Default")
      (node (ref "R26") (pin "2") (pinfunction "2_2") (pintype "input"))
      (node (ref "U1") (pin "11") (pinfunction "–OUT_11") (pintype "input"))
    )
    (net (code "57") (name "Net-(U2-FB{slash}SNS)") (class "Default")
      (node (ref "R28") (pin "2") (pinfunction "2_2") (pintype "input"))
      (node (ref "R29") (pin "1") (pinfunction "1_1") (pintype "input"))
      (node (ref "U2") (pin "3") (pinfunction "FB/SNS_3") (pintype "input"))
    )
    (net (code "58") (name "Net-(U2-NR)") (class "Default")
      (node (ref "C20") (pin "2") (pinfunction "2_2") (pintype "input"))
      (node (ref "U2") (pin "6") (pinfunction "NR_6") (pintype "input"))
    )
    (net (code "59") (name "Net-(U4-MODE)") (class "Default")
      (node (ref "R11") (pin "2") (pinfunction "2_2") (pintype "input"))
      (node (ref "R12") (pin "1") (pinfunction "1_1") (pintype "input"))
      (node (ref "U4") (pin "58") (pinfunction "MODE_58") (pintype "input"))
    )
    (net (code "60") (name "unconnected-(H1-Pad1)") (class "Default")
      (node (ref "H1") (pin "1") (pinfunction "1_1") (pintype "input+no_connect"))
    )
    (net (code "61") (name "unconnected-(H1-Pad2)") (class "Default")
      (node (ref "H1") (pin "2") (pinfunction "2_2") (pintype "input+no_connect"))
    )
    (net (code "62") (name "unconnected-(H3-Pad1)") (class "Default")
      (node (ref "H3") (pin "1") (pinfunction "1_1") (pintype "input+no_connect"))
    )
    (net (code "63") (name "unconnected-(H3-Pad2)") (class "Default")
      (node (ref "H3") (pin "2") (pinfunction "2_2") (pintype "input+no_connect"))
    )
    (net (code "64") (name "unconnected-(U3-NC-Pad4)") (class "Default")
      (node (ref "U3") (pin "4") (pinfunction "NC_4") (pintype "input+no_connect"))
    )
    (net (code "65") (name "unconnected-(U4-CLOCKOUT+{slash}DB11-Pad36)") (class "Default")
      (node (ref "U4") (pin "36") (pinfunction "CLOCKOUT+/DB11_36") (pintype "input+no_connect"))
    )
    (net (code "66") (name "unconnected-(U4-CLOCKOUT–{slash}DB10-Pad35)") (class "Default")
      (node (ref "U4") (pin "35") (pinfunction "CLOCKOUT–/DB10_35") (pintype "input+no_connect"))
    )
    (net (code "67") (name "unconnected-(U4-D1+{slash}DB3-Pad24)") (class "Default")
      (node (ref "U4") (pin "24") (pinfunction "D1+/DB3_24") (pintype "input+no_connect"))
    )
    (net (code "68") (name "unconnected-(U4-D1–{slash}DB2-Pad23)") (class "Default")
      (node (ref "U4") (pin "23") (pinfunction "D1–/DB2_23") (pintype "input+no_connect"))
    )
    (net (code "69") (name "unconnected-(U4-D2+{slash}DB5-Pad28)") (class "Default")
      (node (ref "U4") (pin "28") (pinfunction "D2+/DB5_28") (pintype "input+no_connect"))
    )
    (net (code "70") (name "unconnected-(U4-D2–{slash}DB4-Pad27)") (class "Default")
      (node (ref "U4") (pin "27") (pinfunction "D2–/DB4_27") (pintype "input+no_connect"))
    )
    (net (code "71") (name "unconnected-(U4-D3+{slash}DB7-Pad30)") (class "Default")
      (node (ref "U4") (pin "30") (pinfunction "D3+/DB7_30") (pintype "input+no_connect"))
    )
    (net (code "72") (name "unconnected-(U4-D3–{slash}DB6-Pad29)") (class "Default")
      (node (ref "U4") (pin "29") (pinfunction "D3–/DB6_29") (pintype "input+no_connect"))
    )
    (net (code "73") (name "unconnected-(U4-D4+{slash}DB9-Pad32)") (class "Default")
      (node (ref "U4") (pin "32") (pinfunction "D4+/DB9_32") (pintype "input+no_connect"))
    )
    (net (code "74") (name "unconnected-(U4-D4–{slash}DB8-Pad31)") (class "Default")
      (node (ref "U4") (pin "31") (pinfunction "D4–/DB8_31") (pintype "input+no_connect"))
    )
    (net (code "75") (name "unconnected-(U4-D5–{slash}OFB-Pad37)") (class "Default")
      (node (ref "U4") (pin "37") (pinfunction "D5–/OFB_37") (pintype "input+no_connect"))
    )
    (net (code "76") (name "unconnected-(U4-DO+{slash}DB1-Pad22)") (class "Default")
      (node (ref "U4") (pin "22") (pinfunction "DO+/DB1_22") (pintype "input+no_connect"))
    )
    (net (code "77") (name "unconnected-(U4-DO–{slash}DB0-Pad21)") (class "Default")
      (node (ref "U4") (pin "21") (pinfunction "DO–/DB0_21") (pintype "input+no_connect"))
    )
  )
)
